# CC2530Controller.net
KiCad netlist of a schematic drawn in Altium Designer
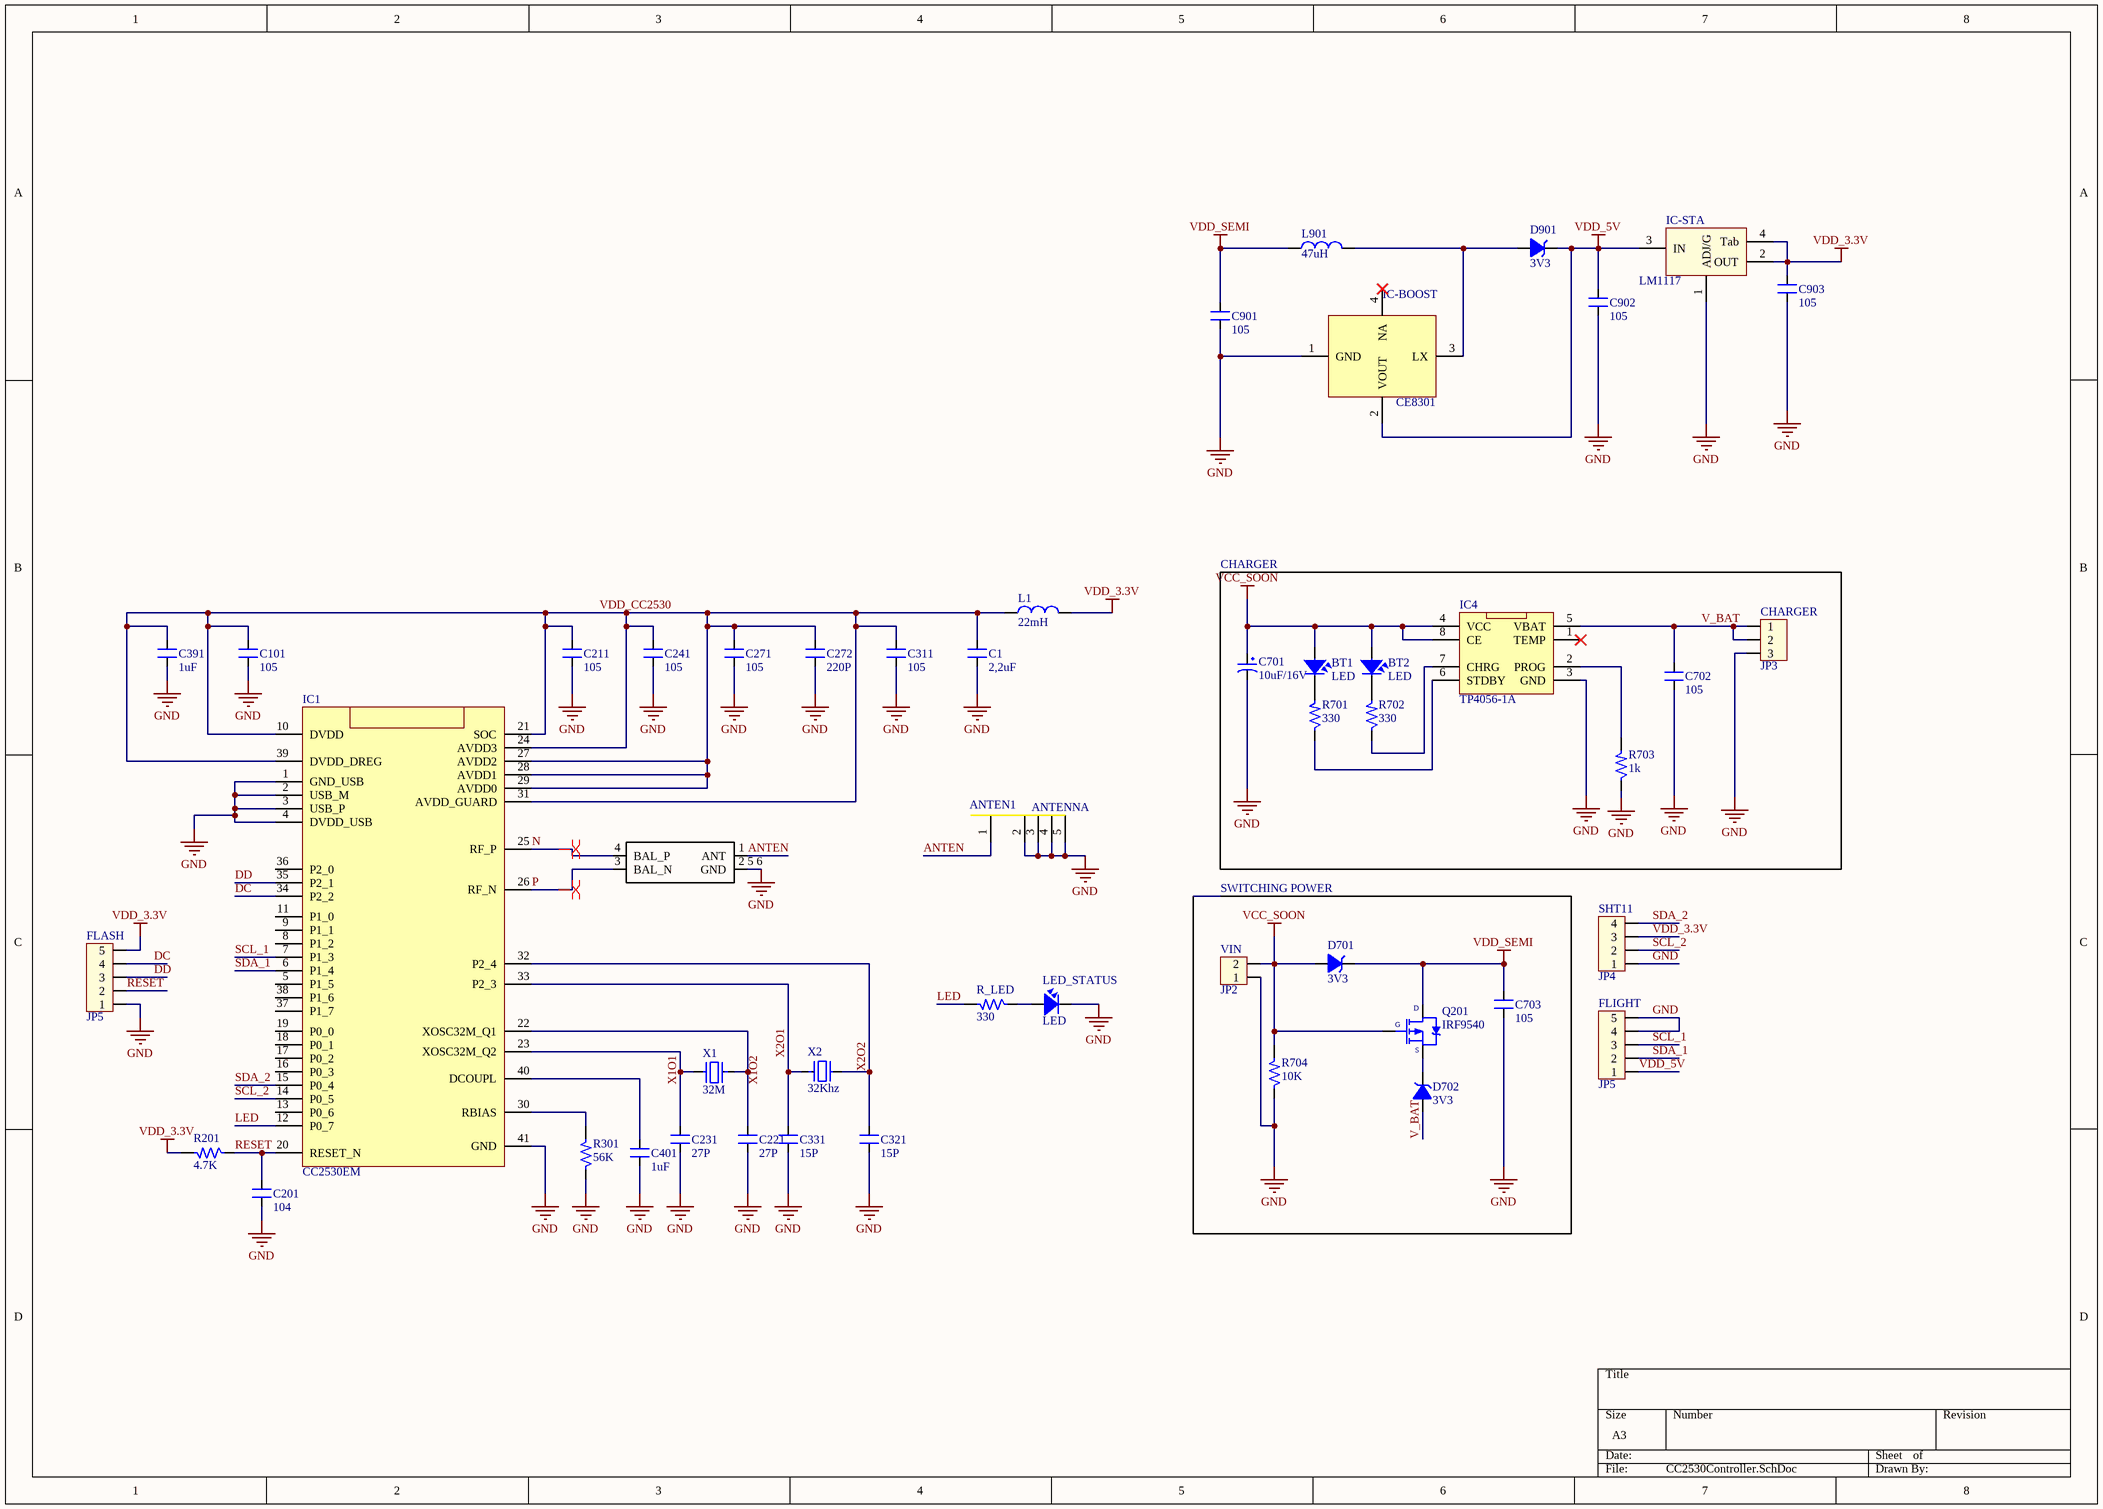
[diagram p0: CC2530Controller.SchDoc]

(export (version "E")
  (design (tool "Eeschema 10.0.6"))
  (components
    (comp (ref "ANTEN1")
      (value "ANTENNA")
      (footprint "ANTEN.08-H5")
      (libsource (lib "khanhct") (part "ANTENNA"))
    )
    (comp (ref "B1")
      (value "2450BM15A0002")
      (footprint "2450BM_2450BM15A0002(Primary)")
      (libsource (lib "khanhct") (part "2450BM15A0002_1"))
    )
    (comp (ref "BT1")
      (value "LED")
      (footprint "LED0805-Blue")
      (description "LED Single colour Green and Red")
      (libsource (lib "syhaunguyen") (part "LED"))
    )
    (comp (ref "BT2")
      (value "LED")
      (footprint "LED0805-Blue")
      (description "LED Single colour Green and Red")
      (libsource (lib "syhaunguyen") (part "LED"))
    )
    (comp (ref "C1")
      (value "2,2uF")
      (footprint "0402 (REFLOW LF)")
      (description "Cap SMD")
      (libsource (lib "syhaunguyen") (part "CM"))
    )
    (comp (ref "C101")
      (value "105")
      (footprint "0402 (REFLOW LF)")
      (description "Cap SMD")
      (libsource (lib "syhaunguyen") (part "CM"))
    )
    (comp (ref "C201")
      (value "104")
      (footprint "0402 (REFLOW LF)")
      (description "Cap SMD")
      (libsource (lib "syhaunguyen") (part "CM"))
    )
    (comp (ref "C211")
      (value "105")
      (footprint "0402 (REFLOW LF)")
      (description "Cap SMD")
      (libsource (lib "syhaunguyen") (part "CM"))
    )
    (comp (ref "C221")
      (value "27P")
      (footprint "0402 (REFLOW)")
      (description "Cap SMD")
      (libsource (lib "syhaunguyen") (part "CM"))
    )
    (comp (ref "C231")
      (value "27P")
      (footprint "0402 (REFLOW)")
      (description "Cap SMD")
      (libsource (lib "syhaunguyen") (part "CM"))
    )
    (comp (ref "C241")
      (value "105")
      (footprint "0402 (REFLOW LF)")
      (description "Cap SMD")
      (libsource (lib "syhaunguyen") (part "CM"))
    )
    (comp (ref "C271")
      (value "105")
      (footprint "0402 (REFLOW LF)")
      (description "Cap SMD")
      (libsource (lib "syhaunguyen") (part "CM"))
    )
    (comp (ref "C272")
      (value "220P")
      (footprint "0402 (REFLOW LF)")
      (description "Cap SMD")
      (libsource (lib "syhaunguyen") (part "CM"))
    )
    (comp (ref "C311")
      (value "105")
      (footprint "0402 (REFLOW LF)")
      (description "Cap SMD")
      (libsource (lib "syhaunguyen") (part "CM"))
    )
    (comp (ref "C321")
      (value "15P")
      (footprint "0402 (REFLOW LF)")
      (description "Cap SMD")
      (libsource (lib "syhaunguyen") (part "CM"))
    )
    (comp (ref "C331")
      (value "15P")
      (footprint "0402 (REFLOW LF)")
      (description "Cap SMD")
      (libsource (lib "syhaunguyen") (part "CM"))
    )
    (comp (ref "C391")
      (value "1uF")
      (footprint "0402 (REFLOW LF)")
      (description "Cap SMD")
      (libsource (lib "syhaunguyen") (part "CM"))
    )
    (comp (ref "C401")
      (value "1uF")
      (footprint "0402 (REFLOW LF)")
      (description "Cap SMD")
      (libsource (lib "syhaunguyen") (part "CM"))
    )
    (comp (ref "C701")
      (value "10uF/16V")
      (footprint "CAP-B-22UF/16V")
      (description "Cap 100uF/35V - 470uF/16V")
      (libsource (lib "syhaunguyen") (part "CP3"))
    )
    (comp (ref "C702")
      (value "105")
      (footprint "0402 (REFLOW LF)")
      (description "Cap SMD")
      (libsource (lib "khanhct") (part "CM"))
    )
    (comp (ref "C703")
      (value "105")
      (footprint "0402 (REFLOW LF)")
      (description "Cap SMD")
      (libsource (lib "khanhct") (part "CM"))
    )
    (comp (ref "C901")
      (value "105")
      (footprint "0402 (REFLOW LF)")
      (description "Cap SMD")
      (libsource (lib "khanhct") (part "CM"))
    )
    (comp (ref "C902")
      (value "105")
      (footprint "0402 (REFLOW LF)")
      (description "Cap SMD")
      (libsource (lib "khanhct") (part "CM"))
    )
    (comp (ref "C903")
      (value "105")
      (footprint "0402 (REFLOW LF)")
      (description "Cap SMD")
      (libsource (lib "khanhct") (part "CM"))
    )
    (comp (ref "CHARGER")
      (value "JP3")
      (footprint "CON3")
      (description "Connector 3")
      (libsource (lib "syhaunguyen") (part "Con3"))
    )
    (comp (ref "D701")
      (value "3V3")
      (footprint "0402 (REFLOW LF)")
      (description "Diode Zenner")
      (libsource (lib "syhaunguyen") (part "DZ"))
    )
    (comp (ref "D702")
      (value "3V3")
      (footprint "0402 (REFLOW LF)")
      (description "Diode Zenner")
      (libsource (lib "syhaunguyen") (part "DZ"))
    )
    (comp (ref "D901")
      (value "3V3")
      (footprint "SS1X-SMD")
      (description "Diode Zenner")
      (libsource (lib "khanhct") (part "DZ"))
    )
    (comp (ref "FLASH")
      (value "JP5")
      (footprint "CON5")
      (description "Connector 5")
      (libsource (lib "khanhct") (part "Con5"))
    )
    (comp (ref "FLIGHT")
      (value "JP5")
      (footprint "CON5")
      (description "Connector 5")
      (libsource (lib "khanhct") (part "Con5"))
    )
    (comp (ref "IC-BOOST")
      (value "CE8301")
      (footprint "SOT89")
      (description "CE8301-SOT-89-3")
      (libsource (lib "khanhct") (part "CE8301"))
    )
    (comp (ref "IC-STA")
      (value "LM1117")
      (footprint "SOT223-4N")
      (description "3v3")
      (libsource (lib "khanhct") (part "LM1117"))
    )
    (comp (ref "IC1")
      (value "CC2530EM")
      (footprint "QLP40 (Reflow)")
      (libsource (lib "syhaunguyen") (part "CC2530EM"))
    )
    (comp (ref "IC4")
      (value "TP4056-1A")
      (footprint "TP4056-1A")
      (libsource (lib "Nupakachi") (part "TP4056-1A"))
    )
    (comp (ref "L1")
      (value "22mH")
      (footprint "0402 (REFLOW LF)")
      (description "Inductor")
      (libsource (lib "syhaunguyen") (part "L1"))
    )
    (comp (ref "L901")
      (value "47uH")
      (footprint "LXX")
      (description "Inductor")
      (libsource (lib "khanhct") (part "L1"))
    )
    (comp (ref "LED_STATUS")
      (value "LED")
      (footprint "SM-0805")
      (description "LED Single colour Green and Red")
      (libsource (lib "khanhct") (part "LED"))
    )
    (comp (ref "Q201")
      (value "IRF9540")
      (footprint "SOT23A")
      (description "HEXFET P-Channel Power MOSFET")
      (fields (field (name "PUBLISHER") "Altium Limited"))
      (libsource (lib "syhaunguyen") (part "IRF9540"))
    )
    (comp (ref "R201")
      (value "4.7K")
      (footprint "0402 (REFLOW LF)")
      (description "Resistor 1/4W")
      (libsource (lib "syhaunguyen") (part "R"))
    )
    (comp (ref "R301")
      (value "56K")
      (footprint "0402 (REFLOW LF)")
      (description "Resistor 1/4W")
      (libsource (lib "syhaunguyen") (part "R"))
    )
    (comp (ref "R701")
      (value "330")
      (footprint "0402 (REFLOW LF)")
      (description "Resistor 1/4W")
      (libsource (lib "syhaunguyen") (part "R"))
    )
    (comp (ref "R702")
      (value "330")
      (footprint "0402 (REFLOW LF)")
      (description "Resistor 1/4W")
      (libsource (lib "syhaunguyen") (part "R"))
    )
    (comp (ref "R703")
      (value "1k")
      (footprint "0402 (REFLOW LF)")
      (description "Resistor 1/4W")
      (libsource (lib "syhaunguyen") (part "R"))
    )
    (comp (ref "R704")
      (value "10K")
      (footprint "0402 (REFLOW LF)")
      (description "Resistor 1/4W")
      (libsource (lib "syhaunguyen") (part "R"))
    )
    (comp (ref "R_LED")
      (value "330")
      (footprint "0402 (REFLOW LF)")
      (description "Resistor 1/4W")
      (libsource (lib "khanhct") (part "R"))
    )
    (comp (ref "SHT11")
      (value "JP4")
      (footprint "CON4")
      (description "Connector 4")
      (libsource (lib "khanhct") (part "Con4"))
    )
    (comp (ref "VIN")
      (value "JP2")
      (footprint "CON2")
      (description "Connector 2")
      (libsource (lib "syhaunguyen") (part "Con2"))
    )
    (comp (ref "X1")
      (value "32M")
      (footprint "XTAL_SMD_3_2x2_5 (3.2 x 2.5 mm)")
      (description "Crystal For all Crystal 2pin.")
      (libsource (lib "syhaunguyen") (part "XT2_SMD_32M"))
    )
    (comp (ref "X2")
      (value "32Khz")
      (footprint "XTAL_SMD_85SMX (8.7x3.8mm)")
      (description "Crystal For all Crystal 2pin.")
      (libsource (lib "syhaunguyen") (part "XT2_SMD_32KHz"))
    )
  )
  (nets
    (net (code "1") (name "/ANTEN") (class "Default")
      (node (ref "ANTEN1") (pin "1") (pintype "passive"))
      (node (ref "B1") (pin "1") (pinfunction "ANT_1") (pintype "bidirectional"))
    )
    (net (code "2") (name "/DC") (class "Default")
      (node (ref "FLASH") (pin "4") (pinfunction "4_4") (pintype "passive"))
      (node (ref "IC1") (pin "34") (pinfunction "P2_2_34") (pintype "passive"))
    )
    (net (code "3") (name "/DD") (class "Default")
      (node (ref "FLASH") (pin "3") (pinfunction "3_3") (pintype "passive"))
      (node (ref "IC1") (pin "35") (pinfunction "P2_1_35") (pintype "passive"))
    )
    (net (code "4") (name "/LED") (class "Default")
      (node (ref "IC1") (pin "12") (pinfunction "P0_7_12") (pintype "passive"))
      (node (ref "R_LED") (pin "2") (pinfunction "2_2") (pintype "passive"))
    )
    (net (code "5") (name "/N") (class "Default")
      (node (ref "B1") (pin "4") (pinfunction "BAL_P_4") (pintype "bidirectional"))
      (node (ref "IC1") (pin "25") (pinfunction "RF_P_25") (pintype "passive"))
    )
    (net (code "6") (name "/P") (class "Default")
      (node (ref "B1") (pin "3") (pinfunction "BAL_N_3") (pintype "bidirectional"))
      (node (ref "IC1") (pin "26") (pinfunction "RF_N_26") (pintype "passive"))
    )
    (net (code "7") (name "/RESET") (class "Default")
      (node (ref "C201") (pin "2") (pinfunction "2_2") (pintype "passive"))
      (node (ref "FLASH") (pin "2") (pinfunction "2_2") (pintype "passive"))
      (node (ref "IC1") (pin "20") (pinfunction "RESET_N_20") (pintype "passive"))
      (node (ref "R201") (pin "1") (pinfunction "1_1") (pintype "passive"))
    )
    (net (code "8") (name "/SCL_1") (class "Default")
      (node (ref "FLIGHT") (pin "3") (pinfunction "3_3") (pintype "passive"))
      (node (ref "IC1") (pin "7") (pinfunction "P1_3_7") (pintype "passive"))
    )
    (net (code "9") (name "/SCL_2") (class "Default")
      (node (ref "IC1") (pin "14") (pinfunction "P0_5_14") (pintype "passive"))
      (node (ref "SHT11") (pin "2") (pinfunction "2_2") (pintype "passive"))
    )
    (net (code "10") (name "/SDA_1") (class "Default")
      (node (ref "FLIGHT") (pin "2") (pinfunction "2_2") (pintype "passive"))
      (node (ref "IC1") (pin "6") (pinfunction "P1_4_6") (pintype "passive"))
    )
    (net (code "11") (name "/SDA_2") (class "Default")
      (node (ref "IC1") (pin "15") (pinfunction "P0_4_15") (pintype "passive"))
      (node (ref "SHT11") (pin "4") (pinfunction "4_4") (pintype "passive"))
    )
    (net (code "12") (name "/VDD_CC2530") (class "Default")
      (node (ref "C1") (pin "2") (pinfunction "2_2") (pintype "passive"))
      (node (ref "C101") (pin "2") (pinfunction "2_2") (pintype "passive"))
      (node (ref "C211") (pin "2") (pinfunction "2_2") (pintype "passive"))
      (node (ref "C241") (pin "2") (pinfunction "2_2") (pintype "passive"))
      (node (ref "C271") (pin "2") (pinfunction "2_2") (pintype "passive"))
      (node (ref "C272") (pin "2") (pinfunction "2_2") (pintype "passive"))
      (node (ref "C311") (pin "2") (pinfunction "2_2") (pintype "passive"))
      (node (ref "C391") (pin "2") (pinfunction "2_2") (pintype "passive"))
      (node (ref "IC1") (pin "10") (pinfunction "DVDD_10") (pintype "passive"))
      (node (ref "IC1") (pin "21") (pinfunction "SOC_21") (pintype "passive"))
      (node (ref "IC1") (pin "24") (pinfunction "AVDD3_24") (pintype "passive"))
      (node (ref "IC1") (pin "27") (pinfunction "AVDD2_27") (pintype "passive"))
      (node (ref "IC1") (pin "28") (pinfunction "AVDD1_28") (pintype "passive"))
      (node (ref "IC1") (pin "29") (pinfunction "AVDD0_29") (pintype "passive"))
      (node (ref "IC1") (pin "31") (pinfunction "AVDD_GUARD_31") (pintype "passive"))
      (node (ref "IC1") (pin "39") (pinfunction "DVDD_DREG_39") (pintype "passive"))
      (node (ref "L1") (pin "1") (pinfunction "1_1") (pintype "passive"))
    )
    (net (code "13") (name "/V_BAT") (class "Default")
      (node (ref "C702") (pin "2") (pinfunction "2_2") (pintype "passive"))
      (node (ref "CHARGER") (pin "1") (pinfunction "1_1") (pintype "passive"))
      (node (ref "CHARGER") (pin "2") (pinfunction "2_2") (pintype "passive"))
      (node (ref "D702") (pin "1") (pinfunction "A_1") (pintype "passive"))
      (node (ref "IC4") (pin "5") (pinfunction "VBAT_5") (pintype "power_in"))
    )
    (net (code "14") (name "/X1O1") (class "Default")
      (node (ref "C231") (pin "2") (pinfunction "2_2") (pintype "passive"))
      (node (ref "IC1") (pin "23") (pinfunction "XOSC32M_Q2_23") (pintype "passive"))
      (node (ref "X1") (pin "1") (pinfunction "1_1") (pintype "passive"))
    )
    (net (code "16") (name "/X2O1") (class "Default")
      (node (ref "C331") (pin "2") (pinfunction "2_2") (pintype "passive"))
      (node (ref "IC1") (pin "33") (pinfunction "P2_3_33") (pintype "passive"))
      (node (ref "X2") (pin "4") (pinfunction "4_4") (pintype "passive"))
    )
    (net (code "17") (name "/X2O2") (class "Default")
      (node (ref "C321") (pin "2") (pinfunction "2_2") (pintype "passive"))
      (node (ref "IC1") (pin "32") (pinfunction "P2_4_32") (pintype "passive"))
      (node (ref "X2") (pin "1") (pinfunction "1_1") (pintype "passive"))
    )
    (net (code "18") (name "GND") (class "Default")
      (node (ref "ANTEN1") (pin "2") (pintype "passive"))
      (node (ref "ANTEN1") (pin "3") (pintype "passive"))
      (node (ref "ANTEN1") (pin "4") (pintype "passive"))
      (node (ref "ANTEN1") (pin "5") (pintype "passive"))
      (node (ref "B1") (pin "2_5_6") (pinfunction "GND_2_5_6") (pintype "bidirectional"))
      (node (ref "C1") (pin "1") (pinfunction "1_1") (pintype "passive"))
      (node (ref "C101") (pin "1") (pinfunction "1_1") (pintype "passive"))
      (node (ref "C201") (pin "1") (pinfunction "1_1") (pintype "passive"))
      (node (ref "C211") (pin "1") (pinfunction "1_1") (pintype "passive"))
      (node (ref "C221") (pin "1") (pinfunction "1_1") (pintype "passive"))
      (node (ref "C231") (pin "1") (pinfunction "1_1") (pintype "passive"))
      (node (ref "C241") (pin "1") (pinfunction "1_1") (pintype "passive"))
      (node (ref "C271") (pin "1") (pinfunction "1_1") (pintype "passive"))
      (node (ref "C272") (pin "1") (pinfunction "1_1") (pintype "passive"))
      (node (ref "C311") (pin "1") (pinfunction "1_1") (pintype "passive"))
      (node (ref "C321") (pin "1") (pinfunction "1_1") (pintype "passive"))
      (node (ref "C331") (pin "1") (pinfunction "1_1") (pintype "passive"))
      (node (ref "C391") (pin "1") (pinfunction "1_1") (pintype "passive"))
      (node (ref "C401") (pin "1") (pinfunction "1_1") (pintype "passive"))
      (node (ref "C701") (pin "2") (pinfunction "2_2") (pintype "passive"))
      (node (ref "C702") (pin "1") (pinfunction "1_1") (pintype "passive"))
      (node (ref "C703") (pin "1") (pinfunction "1_1") (pintype "passive"))
      (node (ref "C901") (pin "2") (pinfunction "2_2") (pintype "passive"))
      (node (ref "C902") (pin "2") (pinfunction "2_2") (pintype "passive"))
      (node (ref "C903") (pin "2") (pinfunction "2_2") (pintype "passive"))
      (node (ref "CHARGER") (pin "3") (pinfunction "3_3") (pintype "passive"))
      (node (ref "FLASH") (pin "1") (pinfunction "1_1") (pintype "passive"))
      (node (ref "FLIGHT") (pin "4") (pinfunction "4_4") (pintype "passive"))
      (node (ref "FLIGHT") (pin "5") (pinfunction "5_5") (pintype "passive"))
      (node (ref "IC-BOOST") (pin "1") (pinfunction "GND_1") (pintype "power_in"))
      (node (ref "IC-STA") (pin "1") (pinfunction "ADJ/G_1") (pintype "passive"))
      (node (ref "IC1") (pin "1") (pinfunction "GND_USB_1") (pintype "power_in"))
      (node (ref "IC1") (pin "2") (pinfunction "USB_M_2") (pintype "passive"))
      (node (ref "IC1") (pin "3") (pinfunction "USB_P_3") (pintype "passive"))
      (node (ref "IC1") (pin "4") (pinfunction "DVDD_USB_4") (pintype "passive"))
      (node (ref "IC1") (pin "41") (pinfunction "GND_41") (pintype "passive"))
      (node (ref "IC4") (pin "3") (pinfunction "GND_3") (pintype "power_in"))
      (node (ref "LED_STATUS") (pin "2") (pinfunction "2_2") (pintype "passive"))
      (node (ref "R301") (pin "1") (pinfunction "1_1") (pintype "passive"))
      (node (ref "R703") (pin "1") (pinfunction "1_1") (pintype "passive"))
      (node (ref "R704") (pin "1") (pinfunction "1_1") (pintype "passive"))
      (node (ref "SHT11") (pin "1") (pinfunction "1_1") (pintype "passive"))
      (node (ref "VIN") (pin "1") (pinfunction "1_1") (pintype "passive"))
    )
    (net (code "19") (name "Net-(BT1-Pad2)") (class "Default")
      (node (ref "BT1") (pin "2") (pinfunction "2_2") (pintype "passive"))
      (node (ref "R701") (pin "2") (pinfunction "2_2") (pintype "passive"))
    )
    (net (code "20") (name "Net-(BT2-Pad2)") (class "Default")
      (node (ref "BT2") (pin "2") (pinfunction "2_2") (pintype "passive"))
      (node (ref "R702") (pin "2") (pinfunction "2_2") (pintype "passive"))
    )
    (net (code "21") (name "Net-(D702-K)") (class "Default")
      (node (ref "D702") (pin "2") (pinfunction "K_2") (pintype "passive"))
      (node (ref "Q201") (pin "3") (pinfunction "S_3") (pintype "passive"))
    )
    (net (code "22") (name "Net-(D901-A)") (class "Default")
      (node (ref "D901") (pin "1") (pinfunction "A_1") (pintype "passive"))
      (node (ref "IC-BOOST") (pin "3") (pinfunction "LX_3") (pintype "passive"))
      (node (ref "L901") (pin "2") (pinfunction "2_2") (pintype "passive"))
    )
    (net (code "23") (name "Net-(IC1-DCOUPL)") (class "Default")
      (node (ref "C401") (pin "2") (pinfunction "2_2") (pintype "passive"))
      (node (ref "IC1") (pin "40") (pinfunction "DCOUPL_40") (pintype "passive"))
    )
    (net (code "24") (name "Net-(IC1-RBIAS)") (class "Default")
      (node (ref "IC1") (pin "30") (pinfunction "RBIAS_30") (pintype "passive"))
      (node (ref "R301") (pin "2") (pinfunction "2_2") (pintype "passive"))
    )
    (net (code "25") (name "Net-(IC1-XOSC32M_Q1)") (class "Default")
      (node (ref "C221") (pin "2") (pinfunction "2_2") (pintype "passive"))
      (node (ref "IC1") (pin "22") (pinfunction "XOSC32M_Q1_22") (pintype "passive"))
      (node (ref "X1") (pin "3") (pinfunction "3_3") (pintype "passive"))
    )
    (net (code "26") (name "Net-(IC4-CHRG)") (class "Default")
      (node (ref "IC4") (pin "7") (pinfunction "CHRG_7") (pintype "passive"))
      (node (ref "R702") (pin "1") (pinfunction "1_1") (pintype "passive"))
    )
    (net (code "27") (name "Net-(IC4-PROG)") (class "Default")
      (node (ref "IC4") (pin "2") (pinfunction "PROG_2") (pintype "passive"))
      (node (ref "R703") (pin "2") (pinfunction "2_2") (pintype "passive"))
    )
    (net (code "28") (name "Net-(IC4-STDBY)") (class "Default")
      (node (ref "IC4") (pin "6") (pinfunction "STDBY_6") (pintype "passive"))
      (node (ref "R701") (pin "1") (pinfunction "1_1") (pintype "passive"))
    )
    (net (code "29") (name "Net-(LED_STATUS-Pad1)") (class "Default")
      (node (ref "LED_STATUS") (pin "1") (pinfunction "1_1") (pintype "passive"))
      (node (ref "R_LED") (pin "1") (pinfunction "1_1") (pintype "passive"))
    )
    (net (code "30") (name "VCC_SOON") (class "Default")
      (node (ref "BT1") (pin "1") (pinfunction "1_1") (pintype "passive"))
      (node (ref "BT2") (pin "1") (pinfunction "1_1") (pintype "passive"))
      (node (ref "C701") (pin "1") (pinfunction "1_1") (pintype "passive"))
      (node (ref "D701") (pin "1") (pinfunction "A_1") (pintype "passive"))
      (node (ref "IC4") (pin "4") (pinfunction "VCC_4") (pintype "power_in"))
      (node (ref "IC4") (pin "8") (pinfunction "CE_8") (pintype "passive"))
      (node (ref "Q201") (pin "1") (pinfunction "G_1") (pintype "passive"))
      (node (ref "R704") (pin "2") (pinfunction "2_2") (pintype "passive"))
      (node (ref "VIN") (pin "2") (pinfunction "2_2") (pintype "passive"))
    )
    (net (code "31") (name "VDD_3.3V") (class "Default")
      (node (ref "C903") (pin "1") (pinfunction "1_1") (pintype "passive"))
      (node (ref "FLASH") (pin "5") (pinfunction "5_5") (pintype "passive"))
      (node (ref "IC-STA") (pin "2") (pinfunction "OUT_2") (pintype "passive"))
      (node (ref "IC-STA") (pin "4") (pinfunction "Tab_4") (pintype "passive"))
      (node (ref "L1") (pin "2") (pinfunction "2_2") (pintype "passive"))
      (node (ref "R201") (pin "2") (pinfunction "2_2") (pintype "passive"))
      (node (ref "SHT11") (pin "3") (pinfunction "3_3") (pintype "passive"))
    )
    (net (code "32") (name "VDD_5V") (class "Default")
      (node (ref "C902") (pin "1") (pinfunction "1_1") (pintype "passive"))
      (node (ref "D901") (pin "2") (pinfunction "K_2") (pintype "passive"))
      (node (ref "FLIGHT") (pin "1") (pinfunction "1_1") (pintype "passive"))
      (node (ref "IC-BOOST") (pin "2") (pinfunction "VOUT_2") (pintype "power_in"))
      (node (ref "IC-STA") (pin "3") (pinfunction "IN_3") (pintype "passive"))
    )
    (net (code "33") (name "VDD_SEMI") (class "Default")
      (node (ref "C703") (pin "2") (pinfunction "2_2") (pintype "passive"))
      (node (ref "C901") (pin "1") (pinfunction "1_1") (pintype "passive"))
      (node (ref "D701") (pin "2") (pinfunction "K_2") (pintype "passive"))
      (node (ref "L901") (pin "1") (pinfunction "1_1") (pintype "passive"))
      (node (ref "Q201") (pin "2") (pinfunction "D_2") (pintype "passive"))
    )
    (net (code "34") (name "unconnected-(IC-BOOST-NA-Pad4)") (class "Default")
      (node (ref "IC-BOOST") (pin "4") (pinfunction "NA_4") (pintype "passive+no_connect"))
    )
    (net (code "35") (name "unconnected-(IC1-P0_0-Pad19)") (class "Default")
      (node (ref "IC1") (pin "19") (pinfunction "P0_0_19") (pintype "passive"))
    )
    (net (code "36") (name "unconnected-(IC1-P0_1-Pad18)") (class "Default")
      (node (ref "IC1") (pin "18") (pinfunction "P0_1_18") (pintype "passive"))
    )
    (net (code "37") (name "unconnected-(IC1-P0_2-Pad17)") (class "Default")
      (node (ref "IC1") (pin "17") (pinfunction "P0_2_17") (pintype "passive"))
    )
    (net (code "38") (name "unconnected-(IC1-P0_3-Pad16)") (class "Default")
      (node (ref "IC1") (pin "16") (pinfunction "P0_3_16") (pintype "passive"))
    )
    (net (code "39") (name "unconnected-(IC1-P0_6-Pad13)") (class "Default")
      (node (ref "IC1") (pin "13") (pinfunction "P0_6_13") (pintype "passive"))
    )
    (net (code "40") (name "unconnected-(IC1-P1_0-Pad11)") (class "Default")
      (node (ref "IC1") (pin "11") (pinfunction "P1_0_11") (pintype "passive"))
    )
    (net (code "41") (name "unconnected-(IC1-P1_1-Pad9)") (class "Default")
      (node (ref "IC1") (pin "9") (pinfunction "P1_1_9") (pintype "passive"))
    )
    (net (code "42") (name "unconnected-(IC1-P1_2-Pad8)") (class "Default")
      (node (ref "IC1") (pin "8") (pinfunction "P1_2_8") (pintype "passive"))
    )
    (net (code "43") (name "unconnected-(IC1-P1_5-Pad5)") (class "Default")
      (node (ref "IC1") (pin "5") (pinfunction "P1_5_5") (pintype "passive"))
    )
    (net (code "44") (name "unconnected-(IC1-P1_6-Pad38)") (class "Default")
      (node (ref "IC1") (pin "38") (pinfunction "P1_6_38") (pintype "passive"))
    )
    (net (code "45") (name "unconnected-(IC1-P1_7-Pad37)") (class "Default")
      (node (ref "IC1") (pin "37") (pinfunction "P1_7_37") (pintype "passive"))
    )
    (net (code "46") (name "unconnected-(IC1-P2_0-Pad36)") (class "Default")
      (node (ref "IC1") (pin "36") (pinfunction "P2_0_36") (pintype "passive"))
    )
    (net (code "47") (name "unconnected-(IC4-TEMP-Pad1)") (class "Default")
      (node (ref "IC4") (pin "1") (pinfunction "TEMP_1") (pintype "passive+no_connect"))
    )
  )
)
